# 12_LED.net
KiCad netlist of a schematic drawn in Altium Designer
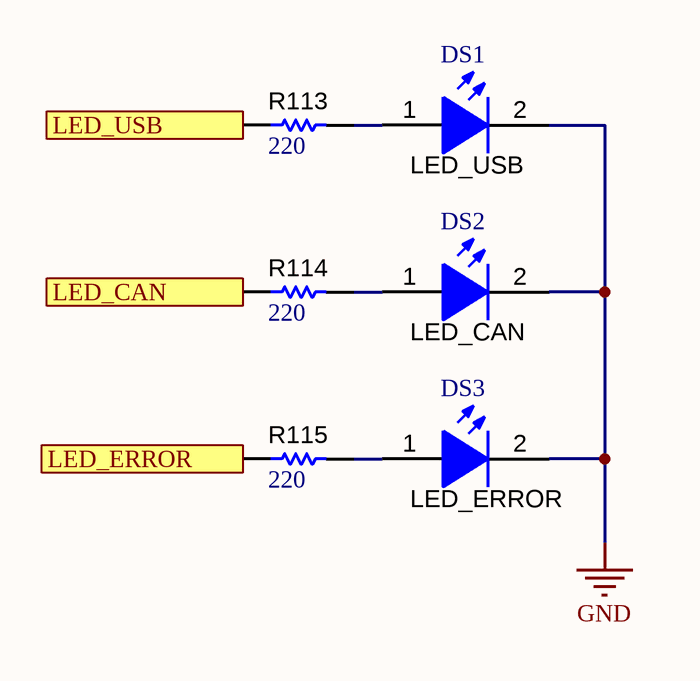
[diagram p0: 12_LED.SchDoc]

(export (version "E")
  (design (tool "Eeschema 10.0.6"))
  (components
    (comp (ref "DS1")
      (value "LED_USB")
      (footprint "LS L29K_Red")
      (description "LED, Red, SMD")
      (fields (field (name "MANUFACTURER") "OSRAM") (field (name "PARTNUMBER") "LS L29K-G1J2-1-Z"))
      (libsource (lib "PROC051C_AWR1843BOOST_RevC") (part "LED RED SMD"))
    )
    (comp (ref "DS2")
      (value "LED_CAN")
      (footprint "LS L29K_Red")
      (description "LED, Red, SMD")
      (fields (field (name "MANUFACTURER") "OSRAM") (field (name "PARTNUMBER") "LS L29K-G1J2-1-Z"))
      (libsource (lib "PROC051C_AWR1843BOOST_RevC") (part "LED RED SMD"))
    )
    (comp (ref "DS3")
      (value "LED_ERROR")
      (footprint "LS L29K_Red")
      (description "LED, Red, SMD")
      (fields (field (name "MANUFACTURER") "OSRAM") (field (name "PARTNUMBER") "LS L29K-G1J2-1-Z"))
      (libsource (lib "PROC051C_AWR1843BOOST_RevC") (part "LED RED SMD"))
    )
    (comp (ref "R113")
      (value "CRCW04021K00FKED")
      (footprint "0402L")
      (description "RES, 1.00 k, 1%, 0.063 W, AEC-Q200 Grade 0, 0402")
      (fields (field (name "MANUFACTURER") "Vishay-Dale") (field (name "VALUEDISPLAYED") "220"))
      (libsource (lib "PROC051C_AWR1843BOOST_RevC") (part "RES 1K 0402"))
    )
    (comp (ref "R114")
      (value "CRCW04021K00FKED")
      (footprint "0402L")
      (description "RES, 1.00 k, 1%, 0.063 W, AEC-Q200 Grade 0, 0402")
      (fields (field (name "MANUFACTURER") "Vishay-Dale") (field (name "VALUEDISPLAYED") "220"))
      (libsource (lib "PROC051C_AWR1843BOOST_RevC") (part "RES 1K 0402"))
    )
    (comp (ref "R115")
      (value "CRCW04021K00FKED")
      (footprint "0402L")
      (description "RES, 1.00 k, 1%, 0.063 W, AEC-Q200 Grade 0, 0402")
      (fields (field (name "MANUFACTURER") "Vishay-Dale") (field (name "VALUEDISPLAYED") "220"))
      (libsource (lib "PROC051C_AWR1843BOOST_RevC") (part "RES 1K 0402"))
    )
  )
  (nets
    (net (code "1") (name "/LED_CAN") (class "Default")
      (node (ref "R114") (pin "1") (pinfunction "1_1") (pintype "passive"))
    )
    (net (code "2") (name "/LED_ERROR") (class "Default")
      (node (ref "R115") (pin "1") (pinfunction "1_1") (pintype "passive"))
    )
    (net (code "3") (name "/LED_USB") (class "Default")
      (node (ref "R113") (pin "1") (pinfunction "1_1") (pintype "passive"))
    )
    (net (code "4") (name "GND") (class "Default")
      (node (ref "DS1") (pin "2") (pinfunction "K_2") (pintype "passive"))
      (node (ref "DS2") (pin "2") (pinfunction "K_2") (pintype "passive"))
      (node (ref "DS3") (pin "2") (pinfunction "K_2") (pintype "passive"))
    )
    (net (code "5") (name "Net-(DS1-A)") (class "Default")
      (node (ref "DS1") (pin "1") (pinfunction "A_1") (pintype "passive"))
      (node (ref "R113") (pin "2") (pinfunction "2_2") (pintype "passive"))
    )
    (net (code "6") (name "Net-(DS2-A)") (class "Default")
      (node (ref "DS2") (pin "1") (pinfunction "A_1") (pintype "passive"))
      (node (ref "R114") (pin "2") (pinfunction "2_2") (pintype "passive"))
    )
    (net (code "7") (name "Net-(DS3-A)") (class "Default")
      (node (ref "DS3") (pin "1") (pinfunction "A_1") (pintype "passive"))
      (node (ref "R115") (pin "2") (pinfunction "2_2") (pintype "passive"))
    )
  )
)
